# EL_Inverter1.net
KiCad netlist of a schematic drawn in EAGLE
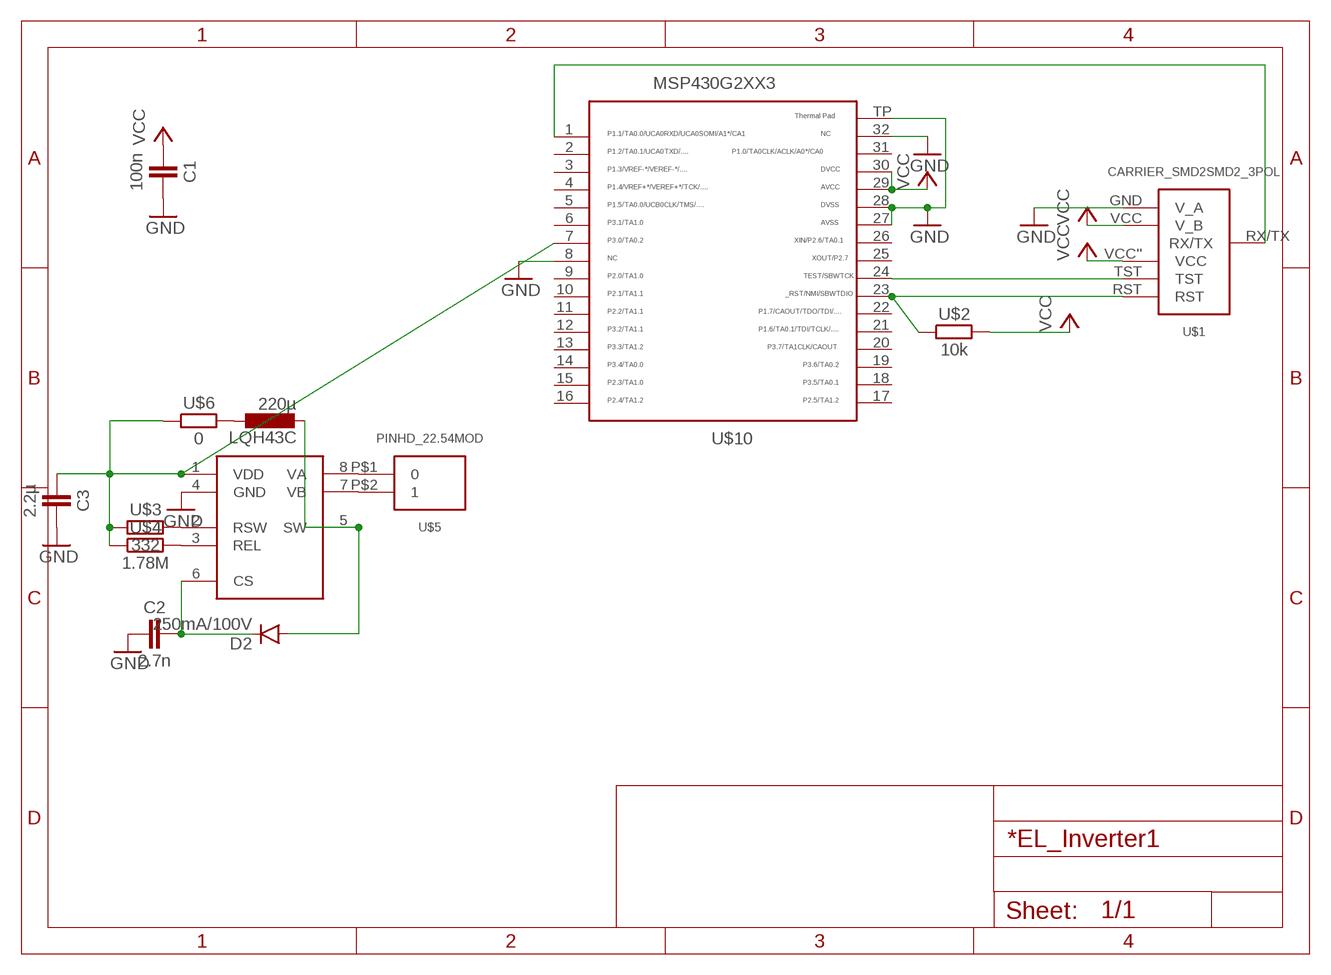
[diagram p0: schematic, sheet 1]

(export (version "E")
  (design (tool "Eeschema 10.0.6"))
  (components
    (comp (ref "C1")
      (value "100n")
      (footprint "eagle-import:603")
      (libsource (lib "eagle-import") (part "CAPACITOR"))
    )
    (comp (ref "C2")
      (value "2.7n")
      (footprint "eagle-import:603")
      (libsource (lib "eagle-import") (part "CAPACITOR"))
    )
    (comp (ref "C3")
      (value "2.2µ")
      (footprint "eagle-import:603")
      (libsource (lib "eagle-import") (part "CAPACITOR"))
    )
    (comp (ref "D2")
      (value "250mA/100V")
      (footprint "eagle-import:SOD-323")
      (libsource (lib "eagle-import") (part "DIODEBAS16"))
    )
    (comp (ref "LQH43C")
      (value "220µ")
      (footprint "eagle-import:L1812")
      (libsource (lib "eagle-import") (part "L-EUL1812"))
    )
    (comp (ref "U$1")
      (value "CARRIER_SMD2SMD2_3POL")
      (footprint "eagle-import:CARRIER_SMD2_3POL")
      (libsource (lib "eagle-import") (part "CARRIER_SMD2SMD2_3POL"))
    )
    (comp (ref "U$2")
      (value "10k")
      (footprint "eagle-import:603")
      (libsource (lib "eagle-import") (part "RESISTOR0603"))
    )
    (comp (ref "U$3")
      (value "332")
      (footprint "eagle-import:603")
      (libsource (lib "eagle-import") (part "RESISTOR0603"))
    )
    (comp (ref "U$4")
      (value "1.78M")
      (footprint "eagle-import:603")
      (libsource (lib "eagle-import") (part "RESISTOR0603"))
    )
    (comp (ref "U$5")
      (value "PINHD_22.54MOD")
      (footprint "eagle-import:PINHD_2_MOD")
      (libsource (lib "eagle-import") (part "PINHD_22.54MOD"))
    )
    (comp (ref "U$6")
      (value "0")
      (footprint "eagle-import:603")
      (libsource (lib "eagle-import") (part "RESISTOR0603"))
    )
    (comp (ref "U$8")
      (value "MIC4830")
      (footprint "eagle-import:MSOP8")
      (libsource (lib "eagle-import") (part "MIC4830"))
    )
    (comp (ref "U$10")
      (value "MSP430G2553")
      (footprint "eagle-import:QFN32")
      (libsource (lib "eagle-import") (part "MSP430G2553"))
    )
  )
  (nets
    (net (code "1") (name "GND") (class "Default")
      (node (ref "C1") (pin "2") (pinfunction "2_2") (pintype "passive"))
      (node (ref "C2") (pin "1") (pinfunction "1_1") (pintype "passive"))
      (node (ref "C3") (pin "2") (pinfunction "2_2") (pintype "passive"))
      (node (ref "U$1") (pin "GND") (pinfunction "V_A_GND") (pintype "bidirectional"))
      (node (ref "U$10") (pin "27") (pinfunction "27_27") (pintype "bidirectional"))
      (node (ref "U$10") (pin "28") (pinfunction "28_28") (pintype "bidirectional"))
      (node (ref "U$10") (pin "32") (pinfunction "32_32") (pintype "bidirectional"))
      (node (ref "U$10") (pin "8") (pinfunction "8_8") (pintype "bidirectional"))
      (node (ref "U$10") (pin "TP") (pinfunction "TP_TP") (pintype "bidirectional"))
      (node (ref "U$8") (pin "4") (pinfunction "GND_4") (pintype "bidirectional"))
    )
    (net (code "2") (name "Net-(LQH43C-Pad1)") (class "Default")
      (node (ref "LQH43C") (pin "1") (pinfunction "1_1") (pintype "passive"))
      (node (ref "U$6") (pin "2") (pinfunction "2_2") (pintype "passive"))
    )
    (net (code "3") (name "Net-(U$1-PadRST)") (class "Default")
      (node (ref "U$1") (pin "RST") (pinfunction "RST_RST") (pintype "bidirectional"))
      (node (ref "U$10") (pin "23") (pinfunction "23_23") (pintype "bidirectional"))
      (node (ref "U$2") (pin "1") (pinfunction "1_1") (pintype "passive"))
    )
    (net (code "4") (name "Net-(U$1-PadRX{slash}TX)") (class "Default")
      (node (ref "U$1") (pin "RX/TX") (pinfunction "RX/TX_RX/TX") (pintype "bidirectional"))
      (node (ref "U$10") (pin "1") (pinfunction "1_1") (pintype "bidirectional"))
    )
    (net (code "5") (name "Net-(U$1-PadTST)") (class "Default")
      (node (ref "U$1") (pin "TST") (pinfunction "TST_TST") (pintype "bidirectional"))
      (node (ref "U$10") (pin "24") (pinfunction "24_24") (pintype "bidirectional"))
    )
    (net (code "6") (name "Net-(U$5-0)") (class "Default")
      (node (ref "U$5") (pin "P$1") (pinfunction "0_P$1") (pintype "bidirectional"))
      (node (ref "U$8") (pin "8") (pinfunction "VA_8") (pintype "bidirectional"))
    )
    (net (code "7") (name "Net-(U$5-1)") (class "Default")
      (node (ref "U$5") (pin "P$2") (pinfunction "1_P$2") (pintype "bidirectional"))
      (node (ref "U$8") (pin "7") (pinfunction "VB_7") (pintype "bidirectional"))
    )
    (net (code "8") (name "Net-(U$8-CS)") (class "Default")
      (node (ref "C2") (pin "2") (pinfunction "2_2") (pintype "passive"))
      (node (ref "D2") (pin "C") (pinfunction "C_C") (pintype "passive"))
      (node (ref "U$8") (pin "6") (pinfunction "CS_6") (pintype "bidirectional"))
    )
    (net (code "9") (name "Net-(U$8-REL)") (class "Default")
      (node (ref "U$4") (pin "2") (pinfunction "2_2") (pintype "passive"))
      (node (ref "U$8") (pin "3") (pinfunction "REL_3") (pintype "bidirectional"))
    )
    (net (code "10") (name "Net-(U$8-RSW)") (class "Default")
      (node (ref "U$3") (pin "2") (pinfunction "2_2") (pintype "passive"))
      (node (ref "U$8") (pin "2") (pinfunction "RSW_2") (pintype "bidirectional"))
    )
    (net (code "11") (name "Net-(U$8-SW)") (class "Default")
      (node (ref "D2") (pin "A") (pinfunction "A_A") (pintype "passive"))
      (node (ref "LQH43C") (pin "2") (pinfunction "2_2") (pintype "passive"))
      (node (ref "U$8") (pin "5") (pinfunction "SW_5") (pintype "bidirectional"))
    )
    (net (code "12") (name "Net-(U$8-VDD)") (class "Default")
      (node (ref "C3") (pin "1") (pinfunction "1_1") (pintype "passive"))
      (node (ref "U$10") (pin "7") (pinfunction "7_7") (pintype "bidirectional"))
      (node (ref "U$3") (pin "1") (pinfunction "1_1") (pintype "passive"))
      (node (ref "U$4") (pin "1") (pinfunction "1_1") (pintype "passive"))
      (node (ref "U$6") (pin "1") (pinfunction "1_1") (pintype "passive"))
      (node (ref "U$8") (pin "1") (pinfunction "VDD_1") (pintype "bidirectional"))
    )
    (net (code "13") (name "VCC") (class "Default")
      (node (ref "C1") (pin "1") (pinfunction "1_1") (pintype "passive"))
      (node (ref "U$1") (pin "VCC") (pinfunction "V_B_VCC") (pintype "bidirectional"))
      (node (ref "U$1") (pin "VCC''") (pinfunction "VCC_VCC''") (pintype "bidirectional"))
      (node (ref "U$10") (pin "29") (pinfunction "29_29") (pintype "bidirectional"))
      (node (ref "U$10") (pin "30") (pinfunction "30_30") (pintype "bidirectional"))
      (node (ref "U$2") (pin "2") (pinfunction "2_2") (pintype "passive"))
    )
    (net (code "14") (name "unconnected-(U$10-Pad2)") (class "Default")
      (node (ref "U$10") (pin "2") (pinfunction "2_2") (pintype "bidirectional"))
    )
    (net (code "15") (name "unconnected-(U$10-Pad3)") (class "Default")
      (node (ref "U$10") (pin "3") (pinfunction "3_3") (pintype "bidirectional"))
    )
    (net (code "16") (name "unconnected-(U$10-Pad4)") (class "Default")
      (node (ref "U$10") (pin "4") (pinfunction "4_4") (pintype "bidirectional"))
    )
    (net (code "17") (name "unconnected-(U$10-Pad5)") (class "Default")
      (node (ref "U$10") (pin "5") (pinfunction "5_5") (pintype "bidirectional"))
    )
    (net (code "18") (name "unconnected-(U$10-Pad6)") (class "Default")
      (node (ref "U$10") (pin "6") (pinfunction "6_6") (pintype "bidirectional"))
    )
    (net (code "19") (name "unconnected-(U$10-Pad9)") (class "Default")
      (node (ref "U$10") (pin "9") (pinfunction "9_9") (pintype "bidirectional"))
    )
    (net (code "20") (name "unconnected-(U$10-Pad10)") (class "Default")
      (node (ref "U$10") (pin "10") (pinfunction "10_10") (pintype "bidirectional"))
    )
    (net (code "21") (name "unconnected-(U$10-Pad11)") (class "Default")
      (node (ref "U$10") (pin "11") (pinfunction "11_11") (pintype "bidirectional"))
    )
    (net (code "22") (name "unconnected-(U$10-Pad12)") (class "Default")
      (node (ref "U$10") (pin "12") (pinfunction "12_12") (pintype "bidirectional"))
    )
    (net (code "23") (name "unconnected-(U$10-Pad13)") (class "Default")
      (node (ref "U$10") (pin "13") (pinfunction "13_13") (pintype "bidirectional"))
    )
    (net (code "24") (name "unconnected-(U$10-Pad14)") (class "Default")
      (node (ref "U$10") (pin "14") (pinfunction "14_14") (pintype "bidirectional"))
    )
    (net (code "25") (name "unconnected-(U$10-Pad15)") (class "Default")
      (node (ref "U$10") (pin "15") (pinfunction "15_15") (pintype "bidirectional"))
    )
    (net (code "26") (name "unconnected-(U$10-Pad16)") (class "Default")
      (node (ref "U$10") (pin "16") (pinfunction "16_16") (pintype "bidirectional"))
    )
    (net (code "27") (name "unconnected-(U$10-Pad17)") (class "Default")
      (node (ref "U$10") (pin "17") (pinfunction "17_17") (pintype "bidirectional"))
    )
    (net (code "28") (name "unconnected-(U$10-Pad18)") (class "Default")
      (node (ref "U$10") (pin "18") (pinfunction "18_18") (pintype "bidirectional"))
    )
    (net (code "29") (name "unconnected-(U$10-Pad19)") (class "Default")
      (node (ref "U$10") (pin "19") (pinfunction "19_19") (pintype "bidirectional"))
    )
    (net (code "30") (name "unconnected-(U$10-Pad20)") (class "Default")
      (node (ref "U$10") (pin "20") (pinfunction "20_20") (pintype "bidirectional"))
    )
    (net (code "31") (name "unconnected-(U$10-Pad21)") (class "Default")
      (node (ref "U$10") (pin "21") (pinfunction "21_21") (pintype "bidirectional"))
    )
    (net (code "32") (name "unconnected-(U$10-Pad22)") (class "Default")
      (node (ref "U$10") (pin "22") (pinfunction "22_22") (pintype "bidirectional"))
    )
    (net (code "33") (name "unconnected-(U$10-Pad25)") (class "Default")
      (node (ref "U$10") (pin "25") (pinfunction "25_25") (pintype "bidirectional"))
    )
    (net (code "34") (name "unconnected-(U$10-Pad26)") (class "Default")
      (node (ref "U$10") (pin "26") (pinfunction "26_26") (pintype "bidirectional"))
    )
    (net (code "35") (name "unconnected-(U$10-Pad31)") (class "Default")
      (node (ref "U$10") (pin "31") (pinfunction "31_31") (pintype "bidirectional"))
    )
  )
)
